# master.net
KiCad netlist of a schematic drawn in Altium Designer
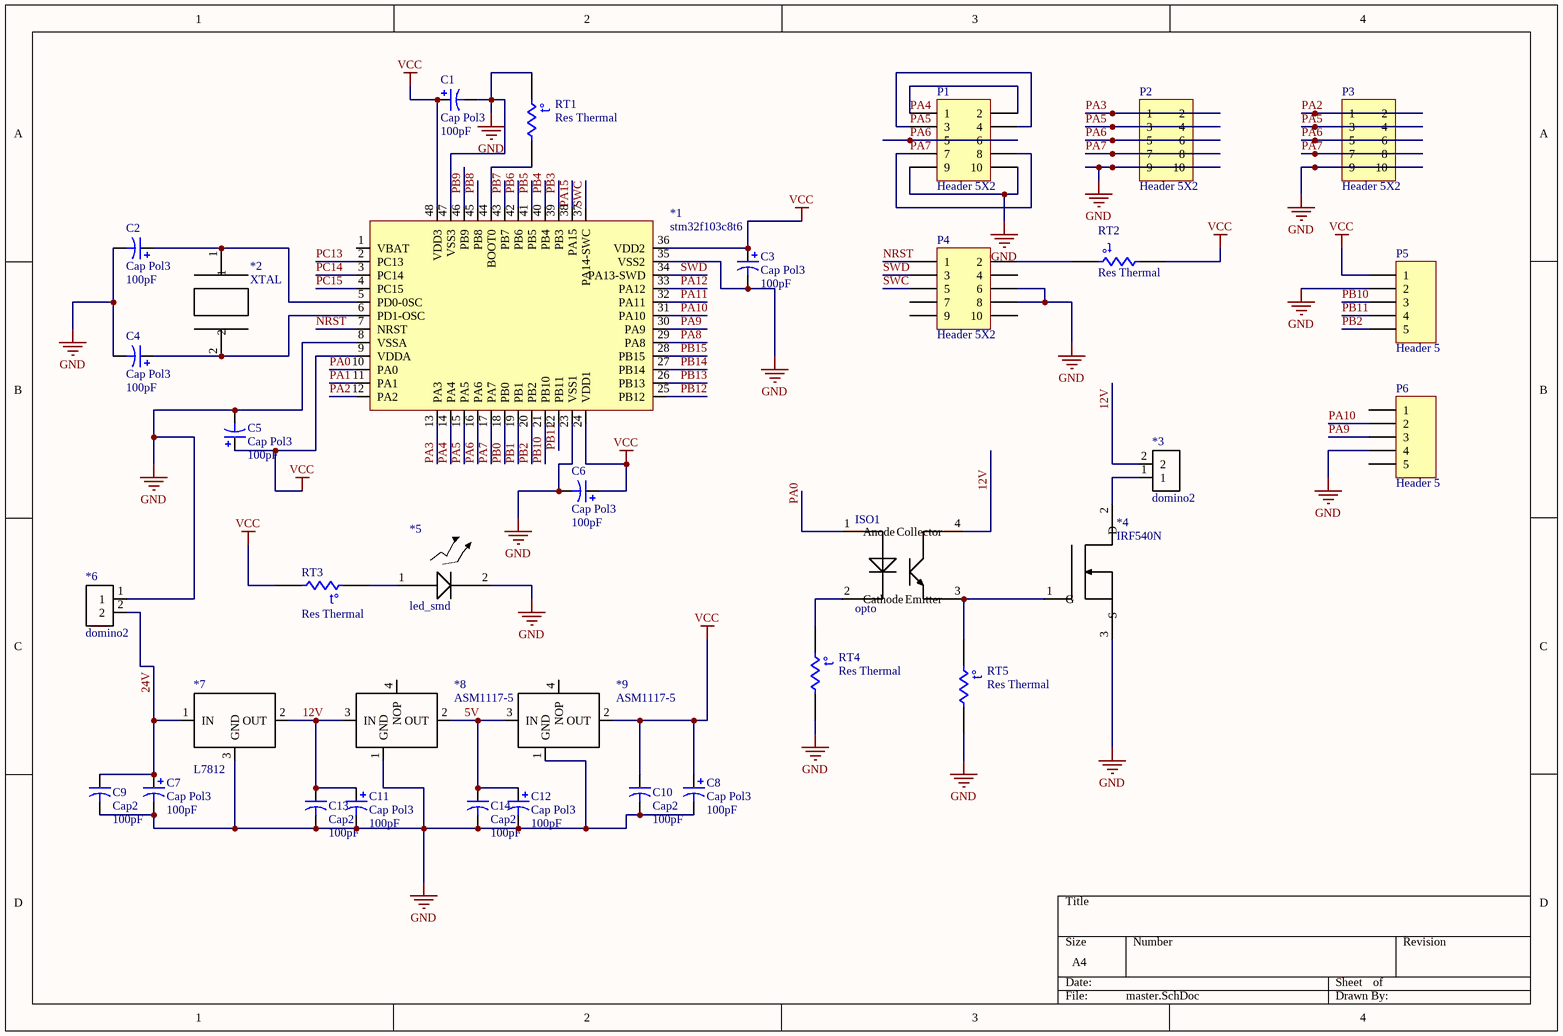
[diagram p0: master.SchDoc]

(export (version "E")
  (design (tool "Eeschema 10.0.6"))
  (components
    (comp (ref "*1")
      (value "stm32f103c8t6")
      (footprint "Pcbforslave:LQFP48_stm32")
      (libsource (lib "Schlib1") (part "stm32f103c8t6"))
    )
    (comp (ref "*2")
      (value "XTAL")
      (footprint "Pcbforslave:xtal_smd")
      (libsource (lib "Schlib1") (part "XTAL"))
    )
    (comp (ref "*3")
      (value "domino2")
      (footprint "Pcbforslave:Domino_2")
      (libsource (lib "Schlib1") (part "domino2"))
    )
    (comp (ref "*4")
      (value "IRF540N")
      (footprint "Pcbforslave:TO220")
      (libsource (lib "Schlib1") (part "IRF540N"))
    )
    (comp (ref "*5")
      (value "led_smd")
      (footprint "Pcbforslave:led_smd")
      (libsource (lib "Schlib1") (part "led_smd"))
    )
    (comp (ref "*6")
      (value "domino2")
      (footprint "Pcbforslave:Domino_2")
      (libsource (lib "Schlib1") (part "domino2"))
    )
    (comp (ref "*7")
      (value "L7812")
      (footprint "Pcbforslave:TO220")
      (libsource (lib "Schlib1") (part "L7812"))
    )
    (comp (ref "*8")
      (value "ASM1117-5")
      (footprint "Pcbforslave:SOT223")
      (libsource (lib "Schlib1") (part "ASM1117-5"))
    )
    (comp (ref "*9")
      (value "ASM1117-5")
      (footprint "Pcbforslave:SOT223")
      (libsource (lib "Schlib1") (part "ASM1117-5"))
    )
    (comp (ref "C1")
      (value "Cap Pol3")
      (footprint "C0805")
      (description "Polarized Capacitor (Surface Mount)")
      (fields (field (name "ALTIUM_VALUE") "100pF") (field (name "PUBLISHER") "Altium Limited"))
      (libsource (lib "Miscellaneous Devices") (part "Cap Pol3"))
    )
    (comp (ref "C2")
      (value "Cap Pol3")
      (footprint "C0805")
      (description "Polarized Capacitor (Surface Mount)")
      (fields (field (name "ALTIUM_VALUE") "100pF") (field (name "PUBLISHER") "Altium Limited"))
      (libsource (lib "Miscellaneous Devices") (part "Cap Pol3"))
    )
    (comp (ref "C3")
      (value "Cap Pol3")
      (footprint "C0805")
      (description "Polarized Capacitor (Surface Mount)")
      (fields (field (name "ALTIUM_VALUE") "100pF") (field (name "PUBLISHER") "Altium Limited"))
      (libsource (lib "Miscellaneous Devices") (part "Cap Pol3"))
    )
    (comp (ref "C4")
      (value "Cap Pol3")
      (footprint "C0805")
      (description "Polarized Capacitor (Surface Mount)")
      (fields (field (name "ALTIUM_VALUE") "100pF") (field (name "PUBLISHER") "Altium Limited"))
      (libsource (lib "Miscellaneous Devices") (part "Cap Pol3"))
    )
    (comp (ref "C5")
      (value "Cap Pol3")
      (footprint "C0805")
      (description "Polarized Capacitor (Surface Mount)")
      (fields (field (name "ALTIUM_VALUE") "100pF") (field (name "PUBLISHER") "Altium Limited"))
      (libsource (lib "Miscellaneous Devices") (part "Cap Pol3"))
    )
    (comp (ref "C6")
      (value "Cap Pol3")
      (footprint "C0805")
      (description "Polarized Capacitor (Surface Mount)")
      (fields (field (name "ALTIUM_VALUE") "100pF") (field (name "PUBLISHER") "Altium Limited"))
      (libsource (lib "Miscellaneous Devices") (part "Cap Pol3"))
    )
    (comp (ref "C7")
      (value "Cap Pol3")
      (footprint "C0805")
      (description "Polarized Capacitor (Surface Mount)")
      (fields (field (name "ALTIUM_VALUE") "100pF") (field (name "PUBLISHER") "Altium Limited"))
      (libsource (lib "Miscellaneous Devices") (part "Cap Pol3"))
    )
    (comp (ref "C8")
      (value "Cap Pol3")
      (footprint "C0805")
      (description "Polarized Capacitor (Surface Mount)")
      (fields (field (name "ALTIUM_VALUE") "100pF") (field (name "PUBLISHER") "Altium Limited"))
      (libsource (lib "Miscellaneous Devices") (part "Cap Pol3"))
    )
    (comp (ref "C9")
      (value "Cap2")
      (footprint "CAPR5-4X5")
      (description "Capacitor")
      (fields (field (name "ALTIUM_VALUE") "100pF") (field (name "PUBLISHER") "Altium Limited"))
      (libsource (lib "Miscellaneous Devices") (part "Cap2"))
    )
    (comp (ref "C10")
      (value "Cap2")
      (footprint "CAPR5-4X5")
      (description "Capacitor")
      (fields (field (name "ALTIUM_VALUE") "100pF") (field (name "PUBLISHER") "Altium Limited"))
      (libsource (lib "Miscellaneous Devices") (part "Cap2"))
    )
    (comp (ref "C11")
      (value "Cap Pol3")
      (footprint "C0805")
      (description "Polarized Capacitor (Surface Mount)")
      (fields (field (name "ALTIUM_VALUE") "100pF") (field (name "PUBLISHER") "Altium Limited"))
      (libsource (lib "Miscellaneous Devices") (part "Cap Pol3"))
    )
    (comp (ref "C12")
      (value "Cap Pol3")
      (footprint "C0805")
      (description "Polarized Capacitor (Surface Mount)")
      (fields (field (name "ALTIUM_VALUE") "100pF") (field (name "PUBLISHER") "Altium Limited"))
      (libsource (lib "Miscellaneous Devices") (part "Cap Pol3"))
    )
    (comp (ref "C13")
      (value "Cap2")
      (footprint "CAPR5-4X5")
      (description "Capacitor")
      (fields (field (name "ALTIUM_VALUE") "100pF") (field (name "PUBLISHER") "Altium Limited"))
      (libsource (lib "Miscellaneous Devices") (part "Cap2"))
    )
    (comp (ref "C14")
      (value "Cap2")
      (footprint "CAPR5-4X5")
      (description "Capacitor")
      (fields (field (name "ALTIUM_VALUE") "100pF") (field (name "PUBLISHER") "Altium Limited"))
      (libsource (lib "Miscellaneous Devices") (part "Cap2"))
    )
    (comp (ref "ISO1")
      (value "opto")
      (footprint "Pcbforslave:opto_smd")
      (libsource (lib "Schlib1") (part "opto"))
    )
    (comp (ref "P1")
      (value "Header 5X2")
      (footprint "HDR2X5")
      (description "Header, 5-Pin, Dual row")
      (fields (field (name "PUBLISHER") "Altium Limited"))
      (libsource (lib "Miscellaneous Connectors") (part "Header 5X2"))
    )
    (comp (ref "P2")
      (value "Header 5X2")
      (footprint "HDR2X5")
      (description "Header, 5-Pin, Dual row")
      (fields (field (name "PUBLISHER") "Altium Limited"))
      (libsource (lib "Miscellaneous Connectors") (part "Header 5X2"))
    )
    (comp (ref "P3")
      (value "Header 5X2")
      (footprint "HDR2X5")
      (description "Header, 5-Pin, Dual row")
      (fields (field (name "PUBLISHER") "Altium Limited"))
      (libsource (lib "Miscellaneous Connectors") (part "Header 5X2"))
    )
    (comp (ref "P4")
      (value "Header 5X2")
      (footprint "HDR2X5")
      (description "Header, 5-Pin, Dual row")
      (fields (field (name "PUBLISHER") "Altium Limited"))
      (libsource (lib "Miscellaneous Connectors") (part "Header 5X2"))
    )
    (comp (ref "P5")
      (value "Header 5")
      (footprint "HDR1X5")
      (description "Header, 5-Pin")
      (fields (field (name "PUBLISHER") "Altium Limited"))
      (libsource (lib "Miscellaneous Connectors") (part "Header 5"))
    )
    (comp (ref "P6")
      (value "Header 5")
      (footprint "HDR1X5")
      (description "Header, 5-Pin")
      (fields (field (name "PUBLISHER") "Altium Limited"))
      (libsource (lib "Miscellaneous Connectors") (part "Header 5"))
    )
    (comp (ref "RT1")
      (value "Res Thermal")
      (footprint "6-0805_N")
      (description "Thermistor")
      (fields (field (name "PUBLISHER") "Altium Limited"))
      (libsource (lib "Miscellaneous Devices") (part "Res Thermal"))
    )
    (comp (ref "RT2")
      (value "Res Thermal")
      (footprint "6-0805_N")
      (description "Thermistor")
      (fields (field (name "PUBLISHER") "Altium Limited"))
      (libsource (lib "Miscellaneous Devices") (part "Res Thermal"))
    )
    (comp (ref "RT3")
      (value "Res Thermal")
      (footprint "6-0805_N")
      (description "Thermistor")
      (fields (field (name "PUBLISHER") "Altium Limited"))
      (libsource (lib "Miscellaneous Devices") (part "Res Thermal"))
    )
    (comp (ref "RT4")
      (value "Res Thermal")
      (footprint "6-0805_N")
      (description "Thermistor")
      (fields (field (name "PUBLISHER") "Altium Limited"))
      (libsource (lib "Miscellaneous Devices") (part "Res Thermal"))
    )
    (comp (ref "RT5")
      (value "Res Thermal")
      (footprint "6-0805_N")
      (description "Thermistor")
      (fields (field (name "PUBLISHER") "Altium Limited"))
      (libsource (lib "Miscellaneous Devices") (part "Res Thermal"))
    )
  )
  (nets
    (net (code "1") (name "/5V") (class "Default")
      (node (ref "*8") (pin "2") (pinfunction "OUT_2") (pintype "passive"))
      (node (ref "*9") (pin "3") (pinfunction "IN_3") (pintype "passive"))
      (node (ref "C12") (pin "1") (pinfunction "1_1") (pintype "passive"))
      (node (ref "C14") (pin "1") (pinfunction "1_1") (pintype "passive"))
    )
    (net (code "2") (name "/12V") (class "Default")
      (node (ref "*3") (pin "2") (pinfunction "2_2") (pintype "passive"))
      (node (ref "*7") (pin "2") (pinfunction "OUT_2") (pintype "passive"))
      (node (ref "*8") (pin "3") (pinfunction "IN_3") (pintype "passive"))
      (node (ref "C11") (pin "1") (pinfunction "1_1") (pintype "passive"))
      (node (ref "C13") (pin "1") (pinfunction "1_1") (pintype "passive"))
      (node (ref "ISO1") (pin "4") (pinfunction "Collector_4") (pintype "passive"))
    )
    (net (code "3") (name "/24V") (class "Default")
      (node (ref "*6") (pin "2") (pinfunction "2_2") (pintype "passive"))
      (node (ref "*7") (pin "1") (pinfunction "IN_1") (pintype "passive"))
      (node (ref "C7") (pin "1") (pinfunction "1_1") (pintype "passive"))
      (node (ref "C9") (pin "1") (pinfunction "1_1") (pintype "passive"))
    )
    (net (code "4") (name "/NRST") (class "Default")
      (node (ref "*1") (pin "7") (pinfunction "NRST_7") (pintype "passive"))
      (node (ref "P4") (pin "1") (pinfunction "1_1") (pintype "passive"))
    )
    (net (code "5") (name "/PA0") (class "Default")
      (node (ref "*1") (pin "10") (pinfunction "PA0_10") (pintype "passive"))
      (node (ref "ISO1") (pin "1") (pinfunction "Anode_1") (pintype "passive"))
    )
    (net (code "6") (name "/PA1") (class "Default")
      (node (ref "*1") (pin "11") (pinfunction "PA1_11") (pintype "passive"))
    )
    (net (code "7") (name "/PA2") (class "Default")
      (node (ref "*1") (pin "12") (pinfunction "PA2_12") (pintype "passive"))
      (node (ref "P3") (pin "1") (pinfunction "1_1") (pintype "passive"))
      (node (ref "P3") (pin "2") (pinfunction "2_2") (pintype "passive"))
    )
    (net (code "8") (name "/PA3") (class "Default")
      (node (ref "*1") (pin "13") (pinfunction "PA3_13") (pintype "passive"))
      (node (ref "P2") (pin "1") (pinfunction "1_1") (pintype "passive"))
      (node (ref "P2") (pin "2") (pinfunction "2_2") (pintype "passive"))
    )
    (net (code "9") (name "/PA4") (class "Default")
      (node (ref "*1") (pin "14") (pinfunction "PA4_14") (pintype "passive"))
      (node (ref "P1") (pin "1") (pinfunction "1_1") (pintype "passive"))
      (node (ref "P1") (pin "2") (pinfunction "2_2") (pintype "passive"))
    )
    (net (code "10") (name "/PA5") (class "Default")
      (node (ref "*1") (pin "15") (pinfunction "PA5_15") (pintype "passive"))
      (node (ref "P1") (pin "3") (pinfunction "3_3") (pintype "passive"))
      (node (ref "P1") (pin "4") (pinfunction "4_4") (pintype "passive"))
      (node (ref "P2") (pin "3") (pinfunction "3_3") (pintype "passive"))
      (node (ref "P2") (pin "4") (pinfunction "4_4") (pintype "passive"))
      (node (ref "P3") (pin "3") (pinfunction "3_3") (pintype "passive"))
      (node (ref "P3") (pin "4") (pinfunction "4_4") (pintype "passive"))
    )
    (net (code "11") (name "/PA6") (class "Default")
      (node (ref "*1") (pin "16") (pinfunction "PA6_16") (pintype "passive"))
      (node (ref "P1") (pin "5") (pinfunction "5_5") (pintype "passive"))
      (node (ref "P1") (pin "6") (pinfunction "6_6") (pintype "passive"))
      (node (ref "P2") (pin "5") (pinfunction "5_5") (pintype "passive"))
      (node (ref "P2") (pin "6") (pinfunction "6_6") (pintype "passive"))
      (node (ref "P3") (pin "5") (pinfunction "5_5") (pintype "passive"))
      (node (ref "P3") (pin "6") (pinfunction "6_6") (pintype "passive"))
    )
    (net (code "12") (name "/PA7") (class "Default")
      (node (ref "*1") (pin "17") (pinfunction "PA7_17") (pintype "passive"))
      (node (ref "P1") (pin "7") (pinfunction "7_7") (pintype "passive"))
      (node (ref "P1") (pin "8") (pinfunction "8_8") (pintype "passive"))
      (node (ref "P2") (pin "7") (pinfunction "7_7") (pintype "passive"))
      (node (ref "P2") (pin "8") (pinfunction "8_8") (pintype "passive"))
      (node (ref "P3") (pin "7") (pinfunction "7_7") (pintype "passive"))
      (node (ref "P3") (pin "8") (pinfunction "8_8") (pintype "passive"))
    )
    (net (code "13") (name "/PA8") (class "Default")
      (node (ref "*1") (pin "29") (pinfunction "PA8_29") (pintype "passive"))
    )
    (net (code "14") (name "/PA9") (class "Default")
      (node (ref "*1") (pin "30") (pinfunction "PA9_30") (pintype "passive"))
      (node (ref "P6") (pin "3") (pinfunction "3_3") (pintype "passive"))
    )
    (net (code "15") (name "/PA10") (class "Default")
      (node (ref "*1") (pin "31") (pinfunction "PA10_31") (pintype "passive"))
      (node (ref "P6") (pin "2") (pinfunction "2_2") (pintype "passive"))
    )
    (net (code "16") (name "/PA11") (class "Default")
      (node (ref "*1") (pin "32") (pinfunction "PA11_32") (pintype "passive"))
    )
    (net (code "17") (name "/PA12") (class "Default")
      (node (ref "*1") (pin "33") (pinfunction "PA12_33") (pintype "passive"))
    )
    (net (code "18") (name "/PA15") (class "Default")
      (node (ref "*1") (pin "38") (pinfunction "PA15_38") (pintype "passive"))
    )
    (net (code "19") (name "/PB0") (class "Default")
      (node (ref "*1") (pin "18") (pinfunction "PB0_18") (pintype "passive"))
    )
    (net (code "20") (name "/PB1") (class "Default")
      (node (ref "*1") (pin "19") (pinfunction "PB1_19") (pintype "passive"))
    )
    (net (code "21") (name "/PB2") (class "Default")
      (node (ref "*1") (pin "20") (pinfunction "PB2_20") (pintype "passive"))
      (node (ref "P5") (pin "5") (pinfunction "5_5") (pintype "passive"))
    )
    (net (code "22") (name "/PB3") (class "Default")
      (node (ref "*1") (pin "39") (pinfunction "PB3_39") (pintype "passive"))
    )
    (net (code "23") (name "/PB4") (class "Default")
      (node (ref "*1") (pin "40") (pinfunction "PB4_40") (pintype "passive"))
    )
    (net (code "24") (name "/PB5") (class "Default")
      (node (ref "*1") (pin "41") (pinfunction "PB5_41") (pintype "passive"))
    )
    (net (code "25") (name "/PB6") (class "Default")
      (node (ref "*1") (pin "42") (pinfunction "PB6_42") (pintype "passive"))
    )
    (net (code "26") (name "/PB7") (class "Default")
      (node (ref "*1") (pin "43") (pinfunction "PB7_43") (pintype "passive"))
    )
    (net (code "27") (name "/PB8") (class "Default")
      (node (ref "*1") (pin "45") (pinfunction "PB8_45") (pintype "passive"))
    )
    (net (code "28") (name "/PB9") (class "Default")
      (node (ref "*1") (pin "46") (pinfunction "PB9_46") (pintype "passive"))
    )
    (net (code "29") (name "/PB10") (class "Default")
      (node (ref "*1") (pin "21") (pinfunction "PB10_21") (pintype "passive"))
      (node (ref "P5") (pin "3") (pinfunction "3_3") (pintype "passive"))
    )
    (net (code "30") (name "/PB11") (class "Default")
      (node (ref "*1") (pin "22") (pinfunction "PB11_22") (pintype "passive"))
      (node (ref "P5") (pin "4") (pinfunction "4_4") (pintype "passive"))
    )
    (net (code "31") (name "/PB12") (class "Default")
      (node (ref "*1") (pin "25") (pinfunction "PB12_25") (pintype "passive"))
    )
    (net (code "32") (name "/PB13") (class "Default")
      (node (ref "*1") (pin "26") (pinfunction "PB13_26") (pintype "passive"))
    )
    (net (code "33") (name "/PB14") (class "Default")
      (node (ref "*1") (pin "27") (pinfunction "PB14_27") (pintype "passive"))
    )
    (net (code "34") (name "/PB15") (class "Default")
      (node (ref "*1") (pin "28") (pinfunction "PB15_28") (pintype "passive"))
    )
    (net (code "35") (name "/PC13") (class "Default")
      (node (ref "*1") (pin "2") (pinfunction "PC13_2") (pintype "passive"))
    )
    (net (code "36") (name "/PC14") (class "Default")
      (node (ref "*1") (pin "3") (pinfunction "PC14_3") (pintype "passive"))
    )
    (net (code "37") (name "/PC15") (class "Default")
      (node (ref "*1") (pin "4") (pinfunction "PC15_4") (pintype "passive"))
    )
    (net (code "38") (name "/SWC") (class "Default")
      (node (ref "*1") (pin "37") (pinfunction "PA14-SWC_37") (pintype "passive"))
      (node (ref "P4") (pin "5") (pinfunction "5_5") (pintype "passive"))
    )
    (net (code "39") (name "/SWD") (class "Default")
      (node (ref "*1") (pin "34") (pinfunction "PA13-SWD_34") (pintype "passive"))
      (node (ref "P4") (pin "3") (pinfunction "3_3") (pintype "passive"))
    )
    (net (code "40") (name "GND") (class "Default")
      (node (ref "*1") (pin "23") (pinfunction "VSS1_23") (pintype "passive"))
      (node (ref "*1") (pin "35") (pinfunction "VSS2_35") (pintype "passive"))
      (node (ref "*1") (pin "47") (pinfunction "VSS3_47") (pintype "passive"))
      (node (ref "*1") (pin "8") (pinfunction "VSSA_8") (pintype "passive"))
      (node (ref "*4") (pin "3") (pinfunction "S_3") (pintype "passive"))
      (node (ref "*5") (pin "2") (pintype "passive"))
      (node (ref "*6") (pin "1") (pinfunction "1_1") (pintype "passive"))
      (node (ref "*7") (pin "3") (pinfunction "GND_3") (pintype "passive"))
      (node (ref "*8") (pin "1") (pinfunction "GND_1") (pintype "passive"))
      (node (ref "*9") (pin "1") (pinfunction "GND_1") (pintype "passive"))
      (node (ref "C1") (pin "2") (pinfunction "2_2") (pintype "passive"))
      (node (ref "C10") (pin "2") (pinfunction "2_2") (pintype "passive"))
      (node (ref "C11") (pin "2") (pinfunction "2_2") (pintype "passive"))
      (node (ref "C12") (pin "2") (pinfunction "2_2") (pintype "passive"))
      (node (ref "C13") (pin "2") (pinfunction "2_2") (pintype "passive"))
      (node (ref "C14") (pin "2") (pinfunction "2_2") (pintype "passive"))
      (node (ref "C2") (pin "2") (pinfunction "2_2") (pintype "passive"))
      (node (ref "C3") (pin "2") (pinfunction "2_2") (pintype "passive"))
      (node (ref "C4") (pin "2") (pinfunction "2_2") (pintype "passive"))
      (node (ref "C5") (pin "2") (pinfunction "2_2") (pintype "passive"))
      (node (ref "C6") (pin "2") (pinfunction "2_2") (pintype "passive"))
      (node (ref "C7") (pin "2") (pinfunction "2_2") (pintype "passive"))
      (node (ref "C8") (pin "2") (pinfunction "2_2") (pintype "passive"))
      (node (ref "C9") (pin "2") (pinfunction "2_2") (pintype "passive"))
      (node (ref "P1") (pin "10") (pinfunction "10_10") (pintype "passive"))
      (node (ref "P1") (pin "9") (pinfunction "9_9") (pintype "passive"))
      (node (ref "P2") (pin "10") (pinfunction "10_10") (pintype "passive"))
      (node (ref "P2") (pin "9") (pinfunction "9_9") (pintype "passive"))
      (node (ref "P3") (pin "10") (pinfunction "10_10") (pintype "passive"))
      (node (ref "P3") (pin "9") (pinfunction "9_9") (pintype "passive"))
      (node (ref "P4") (pin "6") (pinfunction "6_6") (pintype "passive"))
      (node (ref "P4") (pin "8") (pinfunction "8_8") (pintype "passive"))
      (node (ref "P5") (pin "2") (pinfunction "2_2") (pintype "passive"))
      (node (ref "P6") (pin "4") (pinfunction "4_4") (pintype "passive"))
      (node (ref "RT1") (pin "1") (pinfunction "1_1") (pintype "passive"))
      (node (ref "RT4") (pin "2") (pinfunction "2_2") (pintype "passive"))
      (node (ref "RT5") (pin "2") (pinfunction "2_2") (pintype "passive"))
    )
    (net (code "41") (name "Net-(*1-BOOT0)") (class "Default")
      (node (ref "*1") (pin "44") (pinfunction "BOOT0_44") (pintype "passive"))
      (node (ref "RT1") (pin "2") (pinfunction "2_2") (pintype "passive"))
    )
    (net (code "42") (name "Net-(*1-PD0-0SC)") (class "Default")
      (node (ref "*1") (pin "5") (pinfunction "PD0-0SC_5") (pintype "passive"))
      (node (ref "*2") (pin "1") (pinfunction "1_1") (pintype "passive"))
      (node (ref "C2") (pin "1") (pinfunction "1_1") (pintype "passive"))
    )
    (net (code "43") (name "Net-(*1-PD1-OSC)") (class "Default")
      (node (ref "*1") (pin "6") (pinfunction "PD1-OSC_6") (pintype "passive"))
      (node (ref "*2") (pin "2") (pinfunction "2_2") (pintype "passive"))
      (node (ref "C4") (pin "1") (pinfunction "1_1") (pintype "passive"))
    )
    (net (code "44") (name "Net-(*4-D)") (class "Default")
      (node (ref "*3") (pin "1") (pinfunction "1_1") (pintype "passive"))
      (node (ref "*4") (pin "2") (pinfunction "D_2") (pintype "passive"))
    )
    (net (code "45") (name "Net-(*4-G)") (class "Default")
      (node (ref "*4") (pin "1") (pinfunction "G_1") (pintype "passive"))
      (node (ref "ISO1") (pin "3") (pinfunction "Emitter_3") (pintype "passive"))
      (node (ref "RT5") (pin "1") (pinfunction "1_1") (pintype "passive"))
    )
    (net (code "46") (name "Net-(*5-Pad1)") (class "Default")
      (node (ref "*5") (pin "1") (pintype "passive"))
      (node (ref "RT3") (pin "1") (pinfunction "1_1") (pintype "passive"))
    )
    (net (code "47") (name "Net-(ISO1-Cathode)") (class "Default")
      (node (ref "ISO1") (pin "2") (pinfunction "Cathode_2") (pintype "passive"))
      (node (ref "RT4") (pin "1") (pinfunction "1_1") (pintype "passive"))
    )
    (net (code "48") (name "Net-(P4-Pad2)") (class "Default")
      (node (ref "P4") (pin "2") (pinfunction "2_2") (pintype "passive"))
      (node (ref "RT2") (pin "1") (pinfunction "1_1") (pintype "passive"))
    )
    (net (code "49") (name "VCC") (class "Default")
      (node (ref "*1") (pin "24") (pinfunction "VDD1_24") (pintype "passive"))
      (node (ref "*1") (pin "36") (pinfunction "VDD2_36") (pintype "passive"))
      (node (ref "*1") (pin "48") (pinfunction "VDD3_48") (pintype "passive"))
      (node (ref "*1") (pin "9") (pinfunction "VDDA_9") (pintype "passive"))
      (node (ref "*9") (pin "2") (pinfunction "OUT_2") (pintype "passive"))
      (node (ref "C1") (pin "1") (pinfunction "1_1") (pintype "passive"))
      (node (ref "C10") (pin "1") (pinfunction "1_1") (pintype "passive"))
      (node (ref "C3") (pin "1") (pinfunction "1_1") (pintype "passive"))
      (node (ref "C5") (pin "1") (pinfunction "1_1") (pintype "passive"))
      (node (ref "C6") (pin "1") (pinfunction "1_1") (pintype "passive"))
      (node (ref "C8") (pin "1") (pinfunction "1_1") (pintype "passive"))
      (node (ref "P5") (pin "1") (pinfunction "1_1") (pintype "passive"))
      (node (ref "RT2") (pin "2") (pinfunction "2_2") (pintype "passive"))
      (node (ref "RT3") (pin "2") (pinfunction "2_2") (pintype "passive"))
    )
    (net (code "50") (name "unconnected-(*1-VBAT-Pad1)") (class "Default")
      (node (ref "*1") (pin "1") (pinfunction "VBAT_1") (pintype "passive"))
    )
    (net (code "51") (name "unconnected-(*8-NOP-Pad4)") (class "Default")
      (node (ref "*8") (pin "4") (pinfunction "NOP_4") (pintype "passive"))
    )
    (net (code "52") (name "unconnected-(*9-NOP-Pad4)") (class "Default")
      (node (ref "*9") (pin "4") (pinfunction "NOP_4") (pintype "passive"))
    )
    (net (code "53") (name "unconnected-(P4-Pad4)") (class "Default")
      (node (ref "P4") (pin "4") (pinfunction "4_4") (pintype "passive"))
    )
    (net (code "54") (name "unconnected-(P4-Pad7)") (class "Default")
      (node (ref "P4") (pin "7") (pinfunction "7_7") (pintype "passive"))
    )
    (net (code "55") (name "unconnected-(P4-Pad9)") (class "Default")
      (node (ref "P4") (pin "9") (pinfunction "9_9") (pintype "passive"))
    )
    (net (code "56") (name "unconnected-(P4-Pad10)") (class "Default")
      (node (ref "P4") (pin "10") (pinfunction "10_10") (pintype "passive"))
    )
    (net (code "57") (name "unconnected-(P6-Pad1)") (class "Default")
      (node (ref "P6") (pin "1") (pinfunction "1_1") (pintype "passive"))
    )
    (net (code "58") (name "unconnected-(P6-Pad5)") (class "Default")
      (node (ref "P6") (pin "5") (pinfunction "5_5") (pintype "passive"))
    )
  )
)
